# Power.net
KiCad netlist of a schematic drawn in Altium Designer
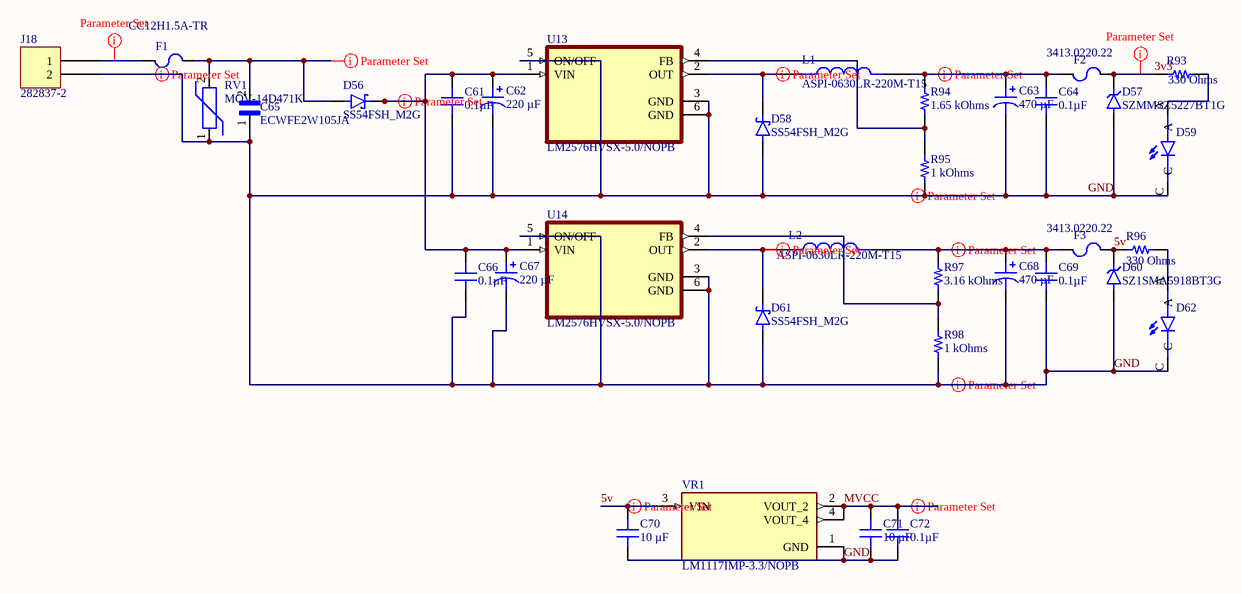
[diagram p0: Power.SchDoc]

(export (version "E")
  (design (tool "Eeschema 10.0.6"))
  (components
    (comp (ref "C61")
      (value "1µF")
      (footprint "CAP 0805_2012")
      (description "CAP CER 1UF 10V X7R 0805")
      (fields
        (field (name "PART NUMBER") "0805ZC105KAT4A")
        (field (name "CAPACITANCE") "0.1µF")
        (field (name "MANUFACTURER") "AVX Corporation")
      )
      (libsource (lib "Celestial Altium Library - altium_library") (part "Capacitor"))
    )
    (comp (ref "C62")
      (value "220 µF")
      (footprint "CAP ALSMD ELEC 8.3MM H11MM")
      (description "CAP ALUM 220UF 20% 35V SMD")
      (fields (field (name "PART NUMBER") "UCH1V221MCS1GS") (field (name "MANUFACTURER") "Nichicon"))
      (libsource (lib "Celestial Altium Library - altium_library") (part "Polarised Capacitor"))
    )
    (comp (ref "C63")
      (value "470 µF")
      (footprint "CAP ALSMD 8.3MM H10.5MM")
      (description "CAP ALUM 470UF 20% 10V SMD")
      (fields (field (name "PART NUMBER") "EMZL100ARA471MHA0G") (field (name "MANUFACTURER") "Chemi-Con"))
      (libsource (lib "Celestial Altium Library - altium_library") (part "Polarised Capacitor"))
    )
    (comp (ref "C64")
      (value "1µF")
      (footprint "CAP 0805_2012")
      (description "CAP CER 1UF 10V X7R 0805")
      (fields
        (field (name "PART NUMBER") "0805ZC105KAT4A")
        (field (name "CAPACITANCE") "0.1µF")
        (field (name "MANUFACTURER") "AVX Corporation")
      )
      (libsource (lib "Celestial Altium Library - altium_library") (part "Capacitor"))
    )
    (comp (ref "C65")
      (value "ECWFE2W105JA")
      (footprint "CAPRR1500W80L1750T700H1250")
      (libsource (lib "ECWFE2W105JA") (part "ECWFE2W105JA"))
    )
    (comp (ref "C66")
      (value "1µF")
      (footprint "CAP 0805_2012")
      (description "CAP CER 1UF 10V X7R 0805")
      (fields
        (field (name "PART NUMBER") "0805ZC105KAT4A")
        (field (name "CAPACITANCE") "0.1µF")
        (field (name "MANUFACTURER") "AVX Corporation")
      )
      (libsource (lib "Celestial Altium Library - altium_library") (part "Capacitor"))
    )
    (comp (ref "C67")
      (value "220 µF")
      (footprint "CAP ALSMD ELEC 8.3MM H11MM")
      (description "CAP ALUM 220UF 20% 35V SMD")
      (fields (field (name "PART NUMBER") "UCH1V221MCS1GS") (field (name "MANUFACTURER") "Nichicon"))
      (libsource (lib "Celestial Altium Library - altium_library") (part "Polarised Capacitor"))
    )
    (comp (ref "C68")
      (value "470 µF")
      (footprint "CAP ALSMD 8.3MM H10.5MM")
      (description "CAP ALUM 470UF 20% 10V SMD")
      (fields (field (name "PART NUMBER") "EMZL100ARA471MHA0G") (field (name "MANUFACTURER") "Chemi-Con"))
      (libsource (lib "Celestial Altium Library - altium_library") (part "Polarised Capacitor"))
    )
    (comp (ref "C69")
      (value "1µF")
      (footprint "CAP 0805_2012")
      (description "CAP CER 1UF 10V X7R 0805")
      (fields
        (field (name "PART NUMBER") "0805ZC105KAT4A")
        (field (name "CAPACITANCE") "0.1µF")
        (field (name "MANUFACTURER") "AVX Corporation")
      )
      (libsource (lib "Celestial Altium Library - altium_library") (part "Capacitor"))
    )
    (comp (ref "C70")
      (value "10 µF")
      (footprint "MURATA CAP GRM31C 1206_3216")
      (description "CAP CER 10UF 25V X7R 1206")
      (fields
        (field (name "PART NUMBER") "GRM31CR71E106KA12K")
        (field (name "CAPACITANCE") "10 µF")
        (field (name "MANUFACTURER") "Murata Electronics")
      )
      (libsource (lib "Celestial Altium Library - altium_library") (part "Capacitor"))
    )
    (comp (ref "C71")
      (value "10 µF")
      (footprint "MURATA CAP GRM31C 1206_3216")
      (description "CAP CER 10UF 25V X7R 1206")
      (fields
        (field (name "PART NUMBER") "GRM31CR71E106KA12K")
        (field (name "CAPACITANCE") "10 µF")
        (field (name "MANUFACTURER") "Murata Electronics")
      )
      (libsource (lib "Celestial Altium Library - altium_library") (part "Capacitor"))
    )
    (comp (ref "C72")
      (value "1µF")
      (footprint "CAP 0805_2012")
      (description "CAP CER 1UF 10V X7R 0805")
      (fields
        (field (name "PART NUMBER") "0805ZC105KAT4A")
        (field (name "CAPACITANCE") "0.1µF")
        (field (name "MANUFACTURER") "AVX Corporation")
      )
      (libsource (lib "Celestial Altium Library - altium_library") (part "Capacitor"))
    )
    (comp (ref "D56")
      (value "SS54FSH_M2G")
      (footprint "SODFL4725X110N")
      (description "Schottky Diodes & Rectifiers 5A, 40V, Schottky Rectifier")
      (fields (field (name "MF") "Taiwan Semiconductor") (field (name "MP") "SS54FSH M2G"))
      (libsource (lib "SS54FSH_M2G") (part "SS54FSH_M2G"))
    )
    (comp (ref "D57")
      (value "SZMMSZ5227BT1G")
      (footprint "DIO_SZMMSZ5227BT1G")
      (libsource (lib "SZMMSZ5227BT1G") (part "SZMMSZ5227BT1G"))
    )
    (comp (ref "D58")
      (value "SS54FSH_M2G")
      (footprint "SODFL4725X110N")
      (description "Schottky Diodes & Rectifiers 5A, 40V, Schottky Rectifier")
      (fields (field (name "MF") "Taiwan Semiconductor") (field (name "MP") "SS54FSH M2G"))
      (libsource (lib "SS54FSH_M2G") (part "SS54FSH_M2G"))
    )
    (comp (ref "D59")
      (value "597-3305-607F")
      (footprint "LEDC2012X70N")
      (description "LED Uni-Color Green 4-Pin Chip 0805 T/R")
      (libsource (lib "597-3305-607F") (part "597-3305-607F"))
    )
    (comp (ref "D60")
      (value "SZ1SMA5918BT3G")
      (footprint "DIOM5226X220N")
      (description "Zener Diode 5.1 V 1.5 W Â±5% Surface Mount SMA")
      (fields (field (name "MF") "ON Semiconductor"))
      (libsource (lib "SZ1SMA5918BT3G") (part "SZ1SMA5918BT3G"))
    )
    (comp (ref "D61")
      (value "SS54FSH_M2G")
      (footprint "SODFL4725X110N")
      (description "Schottky Diodes & Rectifiers 5A, 40V, Schottky Rectifier")
      (fields (field (name "MF") "Taiwan Semiconductor") (field (name "MP") "SS54FSH M2G"))
      (libsource (lib "SS54FSH_M2G") (part "SS54FSH_M2G"))
    )
    (comp (ref "D62")
      (value "597-3305-607F")
      (footprint "LEDC2012X70N")
      (description "LED Uni-Color Green 4-Pin Chip 0805 T/R")
      (libsource (lib "597-3305-607F") (part "597-3305-607F"))
    )
    (comp (ref "F1")
      (value "CC12H1.5A-TR")
      (footprint "FUSE 1206_3216 0.6MM")
      (description "FUSE BOARD MOUNT 1.5A 63VDC 1206")
      (fields (field (name "MANUFACTURER") "Eaton - Electronics Division"))
      (libsource (lib "Celestial Altium Library - altium_library") (part "MOUNTED FUSE"))
    )
    (comp (ref "F2")
      (value "3413.0220.22")
      (footprint "FUSE 1206_3216 0.6MM")
      (description "FUSE BOARD MNT 2.5A 32VAC 63VDC")
      (fields (field (name "MANUFACTURER") "Schurter Inc."))
      (libsource (lib "Celestial Altium Library - altium_library") (part "MOUNTED FUSE"))
    )
    (comp (ref "F3")
      (value "3413.0220.22")
      (footprint "FUSE 1206_3216 0.6MM")
      (description "FUSE BOARD MNT 2.5A 32VAC 63VDC")
      (fields (field (name "MANUFACTURER") "Schurter Inc."))
      (libsource (lib "Celestial Altium Library - altium_library") (part "MOUNTED FUSE"))
    )
    (comp (ref "J18")
      (value "282837-2")
      (footprint "TE 282837-2")
      (description "TERM BLK 2P SIDE ENT 5.08MM PCB")
      (fields (field (name "MANUFACTURER") "TE Connectivity AMP Connectors") (field (name "VOLTAGE") "300 V"))
      (libsource (lib "Celestial Altium Library - altium_library") (part "2 Pin"))
    )
    (comp (ref "L1")
      (value "ASPI-0630LR-220M-T15")
      (footprint "IND_ASPI-0630LR-220M-T15")
      (fields (field (name "MF") "{'manufacturer': u'Abracon LLC'}"))
      (libsource (lib "ASPI-0630LR-220M-T15") (part "ASPI-0630LR-220M-T15"))
    )
    (comp (ref "L2")
      (value "ASPI-0630LR-220M-T15")
      (footprint "IND_ASPI-0630LR-220M-T15")
      (fields (field (name "MF") "{'manufacturer': u'Abracon LLC'}"))
      (libsource (lib "ASPI-0630LR-220M-T15") (part "ASPI-0630LR-220M-T15"))
    )
    (comp (ref "R93")
      (value "330 Ohms")
      (footprint "RES 0805_2012")
      (description "RES SMD 330 OHM 0.1% 1/4W 0805")
      (fields
        (field (name "PART NUMBER") "ERJ-PB6B3300V")
        (field (name "MANUFACTURER") "Panasonic Electronic Components")
      )
      (libsource (lib "Celestial Altium Library - altium_library") (part "Resistor"))
    )
    (comp (ref "R94")
      (value "1.65 kOhms")
      (footprint "RES 0805_2012")
      (description "RES SMD 1.65K OHM 1% 1/8W 0805")
      (fields (field (name "PART NUMBER") "KTR10EZPF1651") (field (name "MANUFACTURER") "Rohm Semiconductor"))
      (libsource (lib "Celestial Altium Library - altium_library") (part "Resistor"))
    )
    (comp (ref "R95")
      (value "1 kOhms")
      (footprint "RES 0805_2012")
      (description "RES SMD 1K OHM 1% 0.4W 0805")
      (fields (field (name "PART NUMBER") "ESR10EZPF1001") (field (name "MANUFACTURER") "Rohm Semiconductor"))
      (libsource (lib "Celestial Altium Library - altium_library") (part "Resistor"))
    )
    (comp (ref "R96")
      (value "330 Ohms")
      (footprint "RES 0805_2012")
      (description "RES SMD 330 OHM 0.1% 1/4W 0805")
      (fields
        (field (name "PART NUMBER") "ERJ-PB6B3300V")
        (field (name "MANUFACTURER") "Panasonic Electronic Components")
      )
      (libsource (lib "Celestial Altium Library - altium_library") (part "Resistor"))
    )
    (comp (ref "R97")
      (value "3.16 kOhms")
      (footprint "RES 0805_2012")
      (description "RES SMD 3.16K OHM 1% 1/8W 0805")
      (fields (field (name "PART NUMBER") "CRCW08053K16FKEA") (field (name "MANUFACTURER") "Vishay Dale"))
      (libsource (lib "Celestial Altium Library - altium_library") (part "Resistor"))
    )
    (comp (ref "R98")
      (value "1 kOhms")
      (footprint "RES 0805_2012")
      (description "RES SMD 1K OHM 1% 0.4W 0805")
      (fields (field (name "PART NUMBER") "ESR10EZPF1001") (field (name "MANUFACTURER") "Rohm Semiconductor"))
      (libsource (lib "Celestial Altium Library - altium_library") (part "Resistor"))
    )
    (comp (ref "RV1")
      (value "MOV-14D471K")
      (footprint "MOV14D471K")
      (description "470 V 4.5 kA Varistor 1 Circuit Through Hole Disc 14mm")
      (fields (field (name "MF") "Bourns"))
      (libsource (lib "MOV-14D471K") (part "MOV-14D471K"))
    )
    (comp (ref "U13")
      (value "LM2576HVSX-5.0/NOPB")
      (footprint "VREG_TPS79625KTTR")
      (description "SIMPLE SWITCHERÂ® 4V to 60V, 3A Low Component Count Step-Down Regulator")
      (fields (field (name "MF") "Texas Instruments"))
      (libsource (lib "LM2576HVSX-5.0_NOPB") (part "LM2576HVSX-5.0/NOPB"))
    )
    (comp (ref "U14")
      (value "LM2576HVSX-5.0/NOPB")
      (footprint "VREG_TPS79625KTTR")
      (description "SIMPLE SWITCHERÂ® 4V to 60V, 3A Low Component Count Step-Down Regulator")
      (fields (field (name "MF") "Texas Instruments"))
      (libsource (lib "LM2576HVSX-5.0_NOPB") (part "LM2576HVSX-5.0/NOPB"))
    )
    (comp (ref "VR1")
      (value "LM1117IMP-3.3/NOPB")
      (footprint "VREG_LM1117IMP-3.3/NOPB")
      (description "800-mA 15-V linear voltage regulator")
      (fields (field (name "MF") "Texas Instruments"))
      (libsource (lib "LM1117IMP-3.3_NOPB") (part "LM1117IMP-3.3/NOPB"))
    )
  )
  (nets
    (net (code "1") (name "/3v3") (class "Default")
      (node (ref "D57") (pin "1") (pinfunction "K_1") (pintype "passive"))
      (node (ref "F2") (pin "2") (pintype "passive"))
      (node (ref "R93") (pin "1") (pinfunction "1_1") (pintype "passive"))
    )
    (net (code "2") (name "/5v") (class "Default")
      (node (ref "C70") (pin "2") (pinfunction "2_2") (pintype "passive"))
      (node (ref "D60") (pin "C") (pinfunction "C_C") (pintype "passive"))
      (node (ref "F3") (pin "2") (pintype "passive"))
      (node (ref "R96") (pin "1") (pinfunction "1_1") (pintype "passive"))
      (node (ref "VR1") (pin "3") (pinfunction "VIN_3") (pintype "input"))
    )
    (net (code "3") (name "/GND") (class "Default")
      (node (ref "C61") (pin "1") (pinfunction "1_1") (pintype "passive"))
      (node (ref "C62") (pin "2") (pinfunction "2_2") (pintype "passive"))
      (node (ref "C63") (pin "2") (pinfunction "2_2") (pintype "passive"))
      (node (ref "C64") (pin "1") (pinfunction "1_1") (pintype "passive"))
      (node (ref "C65") (pin "1") (pinfunction "1_1") (pintype "passive"))
      (node (ref "C66") (pin "1") (pinfunction "1_1") (pintype "passive"))
      (node (ref "C67") (pin "2") (pinfunction "2_2") (pintype "passive"))
      (node (ref "C68") (pin "2") (pinfunction "2_2") (pintype "passive"))
      (node (ref "C69") (pin "1") (pinfunction "1_1") (pintype "passive"))
      (node (ref "C70") (pin "1") (pinfunction "1_1") (pintype "passive"))
      (node (ref "C71") (pin "1") (pinfunction "1_1") (pintype "passive"))
      (node (ref "C72") (pin "1") (pinfunction "1_1") (pintype "passive"))
      (node (ref "D57") (pin "2") (pinfunction "A_2") (pintype "passive"))
      (node (ref "D58") (pin "A") (pinfunction "A_A") (pintype "passive"))
      (node (ref "D59") (pin "C") (pinfunction "C_C") (pintype "passive"))
      (node (ref "D60") (pin "A") (pinfunction "A_A") (pintype "passive"))
      (node (ref "D61") (pin "A") (pinfunction "A_A") (pintype "passive"))
      (node (ref "D62") (pin "C") (pinfunction "C_C") (pintype "passive"))
      (node (ref "J18") (pin "2") (pinfunction "2_2") (pintype "passive"))
      (node (ref "R95") (pin "2") (pinfunction "2_2") (pintype "passive"))
      (node (ref "R98") (pin "2") (pinfunction "2_2") (pintype "passive"))
      (node (ref "RV1") (pin "1") (pinfunction "1_1") (pintype "bidirectional"))
      (node (ref "U13") (pin "3") (pinfunction "GND_3") (pintype "power_in"))
      (node (ref "U13") (pin "5") (pinfunction "ON/OFF_5") (pintype "input"))
      (node (ref "U13") (pin "6") (pinfunction "GND_6") (pintype "power_in"))
      (node (ref "U14") (pin "3") (pinfunction "GND_3") (pintype "power_in"))
      (node (ref "U14") (pin "5") (pinfunction "ON/OFF_5") (pintype "input"))
      (node (ref "U14") (pin "6") (pinfunction "GND_6") (pintype "power_in"))
      (node (ref "VR1") (pin "1") (pinfunction "GND_1") (pintype "power_in"))
    )
    (net (code "4") (name "/MVCC") (class "Default")
      (node (ref "C71") (pin "2") (pinfunction "2_2") (pintype "passive"))
      (node (ref "C72") (pin "2") (pinfunction "2_2") (pintype "passive"))
      (node (ref "VR1") (pin "2") (pinfunction "VOUT_2_2") (pintype "output"))
      (node (ref "VR1") (pin "4") (pinfunction "VOUT_4_4") (pintype "output"))
    )
    (net (code "5") (name "Net-(C63-Pad1)") (class "Default")
      (node (ref "C63") (pin "1") (pinfunction "1_1") (pintype "passive"))
      (node (ref "C64") (pin "2") (pinfunction "2_2") (pintype "passive"))
      (node (ref "F2") (pin "1") (pintype "passive"))
      (node (ref "L1") (pin "2") (pinfunction "2_2") (pintype "passive"))
      (node (ref "R94") (pin "1") (pinfunction "1_1") (pintype "passive"))
    )
    (net (code "6") (name "Net-(C65-Pad2)") (class "Default")
      (node (ref "C65") (pin "2") (pinfunction "2_2") (pintype "passive"))
      (node (ref "D56") (pin "A") (pinfunction "A_A") (pintype "passive"))
      (node (ref "F1") (pin "2") (pintype "passive"))
      (node (ref "RV1") (pin "2") (pinfunction "2_2") (pintype "bidirectional"))
    )
    (net (code "7") (name "Net-(C68-Pad1)") (class "Default")
      (node (ref "C68") (pin "1") (pinfunction "1_1") (pintype "passive"))
      (node (ref "C69") (pin "2") (pinfunction "2_2") (pintype "passive"))
      (node (ref "F3") (pin "1") (pintype "passive"))
      (node (ref "L2") (pin "2") (pinfunction "2_2") (pintype "passive"))
      (node (ref "R97") (pin "2") (pinfunction "2_2") (pintype "passive"))
    )
    (net (code "8") (name "Net-(D56-K)") (class "Default")
      (node (ref "C61") (pin "2") (pinfunction "2_2") (pintype "passive"))
      (node (ref "C62") (pin "1") (pinfunction "1_1") (pintype "passive"))
      (node (ref "C66") (pin "2") (pinfunction "2_2") (pintype "passive"))
      (node (ref "C67") (pin "1") (pinfunction "1_1") (pintype "passive"))
      (node (ref "D56") (pin "C") (pinfunction "K_C") (pintype "passive"))
      (node (ref "U13") (pin "1") (pinfunction "VIN_1") (pintype "input"))
      (node (ref "U14") (pin "1") (pinfunction "VIN_1") (pintype "input"))
    )
    (net (code "9") (name "Net-(D58-K)") (class "Default")
      (node (ref "D58") (pin "C") (pinfunction "K_C") (pintype "passive"))
      (node (ref "L1") (pin "1") (pinfunction "1_1") (pintype "passive"))
      (node (ref "U13") (pin "2") (pinfunction "OUT_2") (pintype "output"))
    )
    (net (code "10") (name "Net-(D59-PadA)") (class "Default")
      (node (ref "D59") (pin "A") (pinfunction "A_A") (pintype "passive"))
      (node (ref "R93") (pin "2") (pinfunction "2_2") (pintype "passive"))
    )
    (net (code "11") (name "Net-(D61-K)") (class "Default")
      (node (ref "D61") (pin "C") (pinfunction "K_C") (pintype "passive"))
      (node (ref "L2") (pin "1") (pinfunction "1_1") (pintype "passive"))
      (node (ref "U14") (pin "2") (pinfunction "OUT_2") (pintype "output"))
    )
    (net (code "12") (name "Net-(D62-PadA)") (class "Default")
      (node (ref "D62") (pin "A") (pinfunction "A_A") (pintype "passive"))
      (node (ref "R96") (pin "2") (pinfunction "2_2") (pintype "passive"))
    )
    (net (code "13") (name "Net-(F1-Pad1)") (class "Default")
      (node (ref "F1") (pin "1") (pintype "passive"))
      (node (ref "J18") (pin "1") (pinfunction "1_1") (pintype "passive"))
    )
    (net (code "14") (name "Net-(U13-FB)") (class "Default")
      (node (ref "R94") (pin "2") (pinfunction "2_2") (pintype "passive"))
      (node (ref "R95") (pin "1") (pinfunction "1_1") (pintype "passive"))
      (node (ref "U13") (pin "4") (pinfunction "FB_4") (pintype "output"))
    )
    (net (code "15") (name "Net-(U14-FB)") (class "Default")
      (node (ref "R97") (pin "1") (pinfunction "1_1") (pintype "passive"))
      (node (ref "R98") (pin "1") (pinfunction "1_1") (pintype "passive"))
      (node (ref "U14") (pin "4") (pinfunction "FB_4") (pintype "output"))
    )
  )
)
